# 07_MSM8916_GPIO.net
KiCad netlist of a schematic drawn in Altium Designer
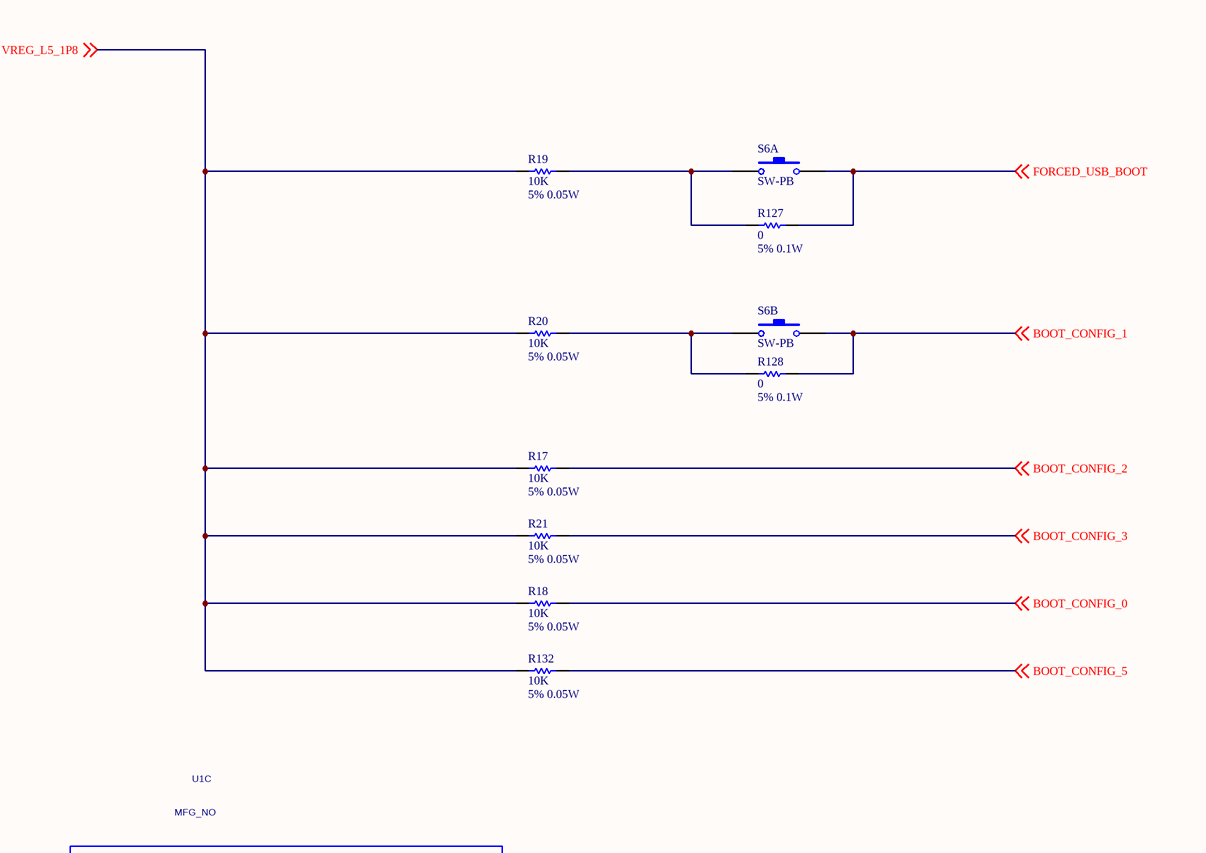
[diagram p0: 07_MSM8916_GPIO.SchDoc, top left]
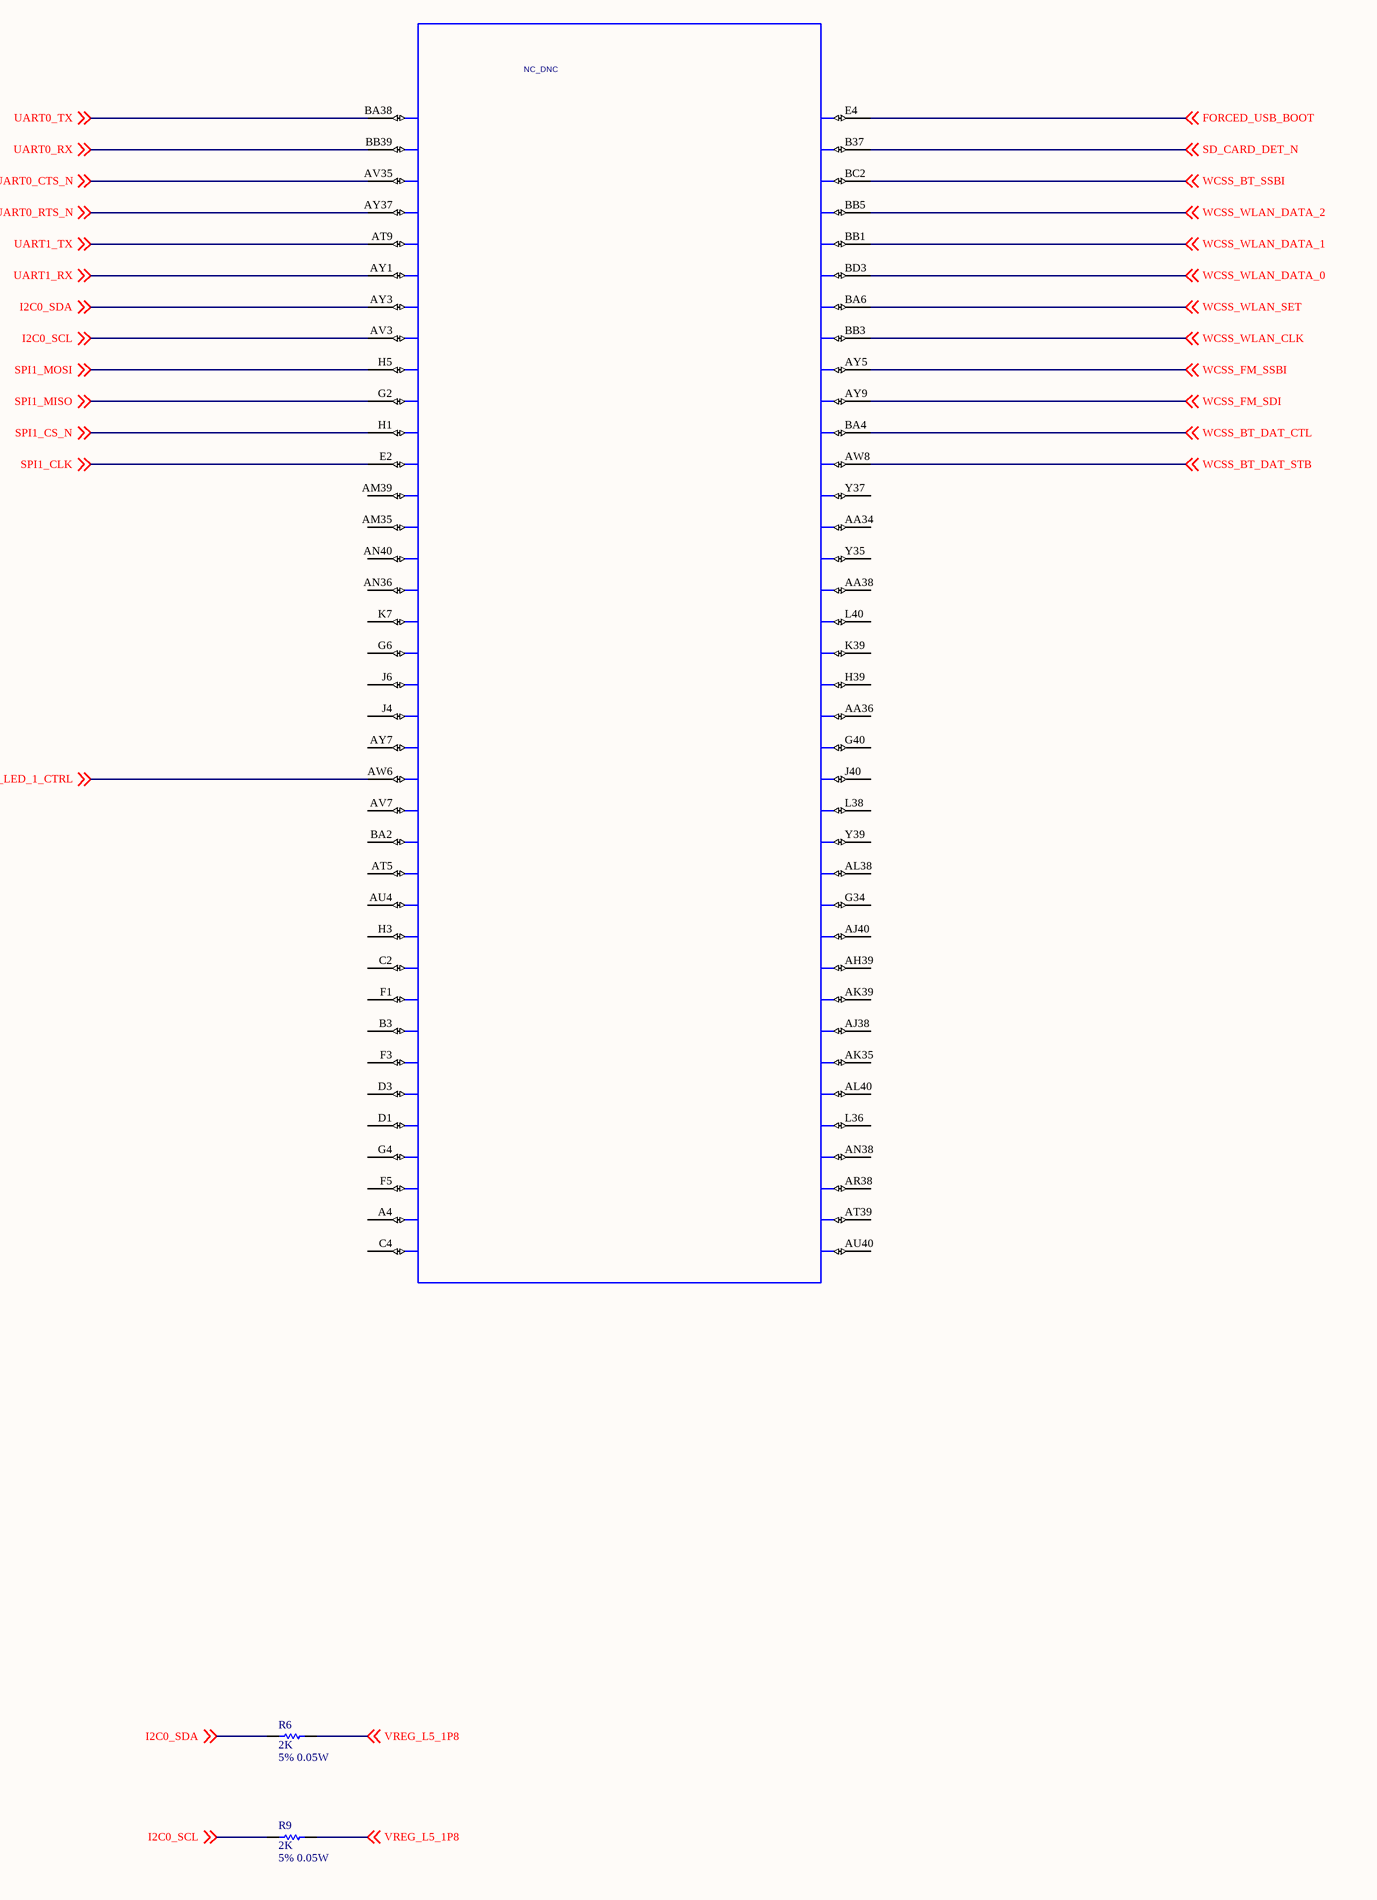
[diagram p1: 07_MSM8916_GPIO.SchDoc, bottom left]
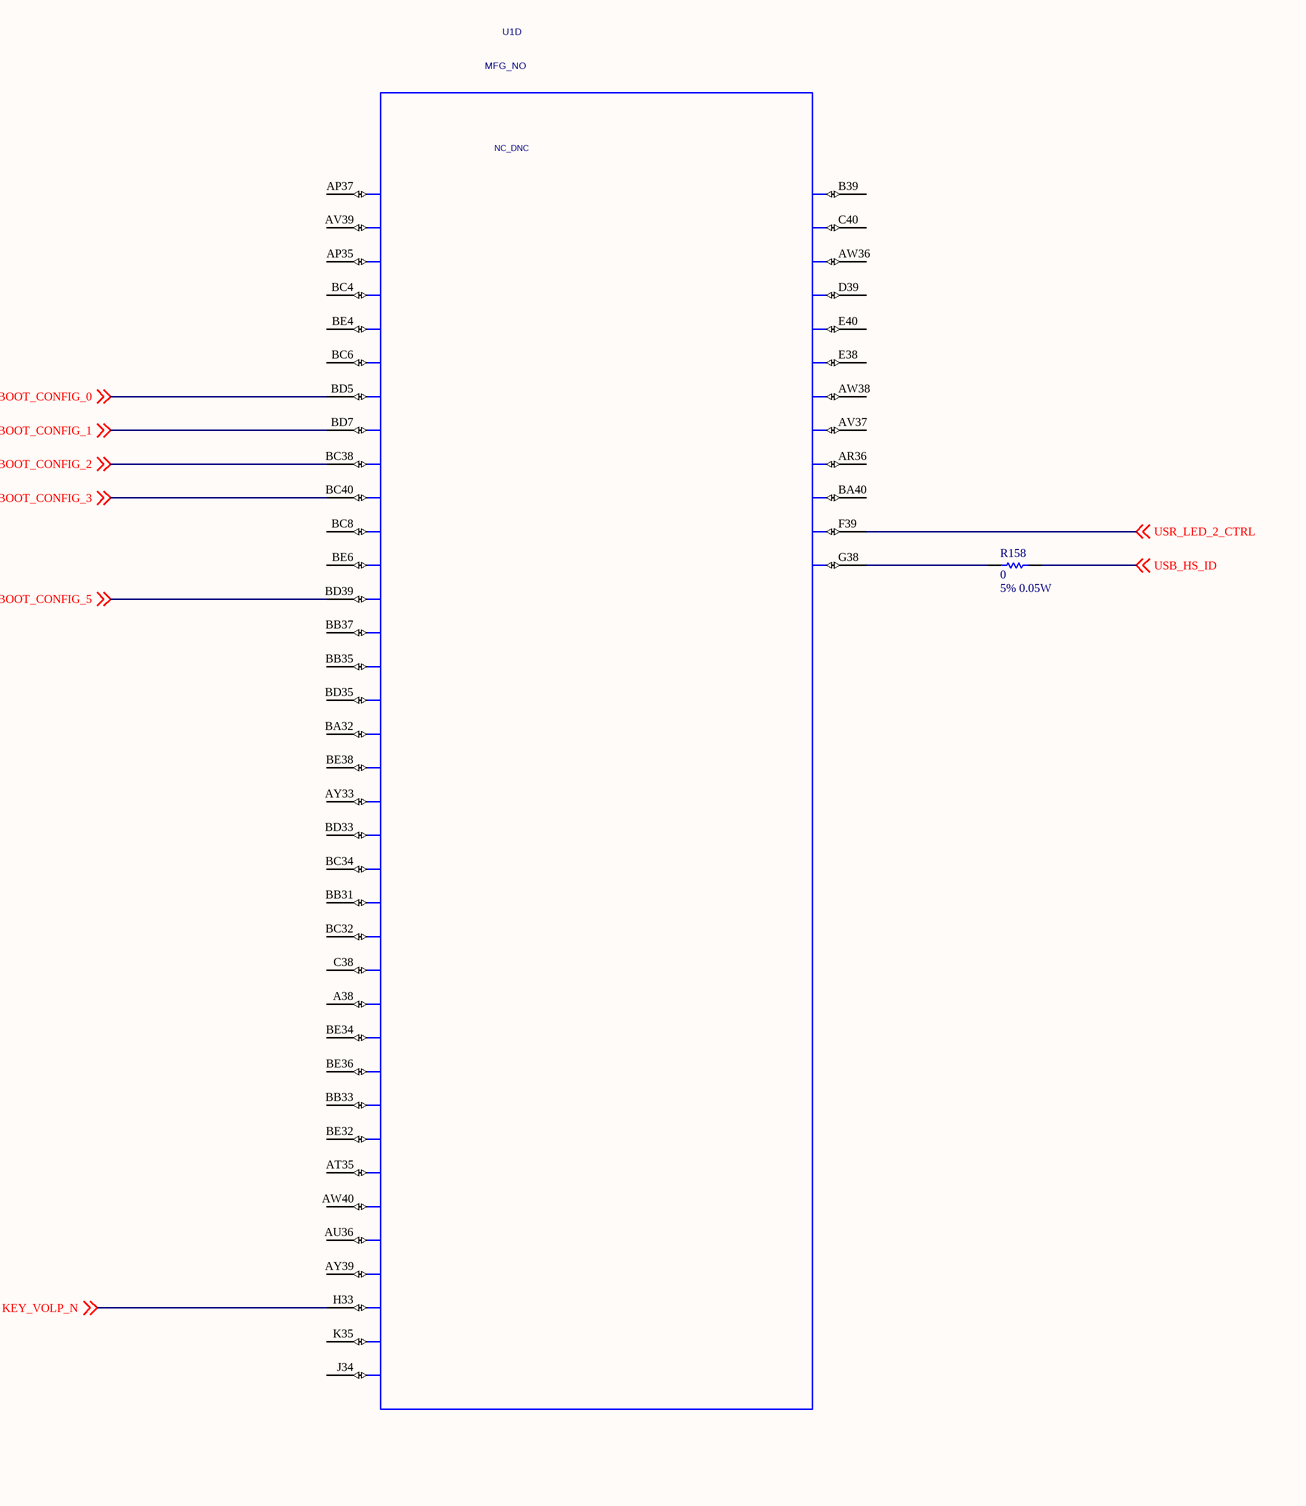
[diagram p2: 07_MSM8916_GPIO.SchDoc, bottom right]

(export (version "E")
  (design (tool "Eeschema 10.0.6"))
  (components
    (comp (ref "R6")
      (value "2K")
      (footprint "AXIAL-0.3")
      (description "Resistor")
      (fields (field (name "ALTIUM_VALUE") "5% 0.05W") (field (name "PUBLISHER") "Altium Limited"))
      (libsource (lib "Miscellaneous Devices") (part "Res1"))
    )
    (comp (ref "R9")
      (value "2K")
      (footprint "AXIAL-0.3")
      (description "Resistor")
      (fields (field (name "ALTIUM_VALUE") "5% 0.05W") (field (name "PUBLISHER") "Altium Limited"))
      (libsource (lib "Miscellaneous Devices") (part "Res1"))
    )
    (comp (ref "R17")
      (value "10K")
      (footprint "AXIAL-0.3")
      (description "Resistor")
      (fields (field (name "ALTIUM_VALUE") "5% 0.05W") (field (name "PUBLISHER") "Altium Limited"))
      (libsource (lib "Miscellaneous Devices") (part "Res1"))
    )
    (comp (ref "R18")
      (value "10K")
      (footprint "AXIAL-0.3")
      (description "Resistor")
      (fields (field (name "ALTIUM_VALUE") "5% 0.05W") (field (name "PUBLISHER") "Altium Limited"))
      (libsource (lib "Miscellaneous Devices") (part "Res1"))
    )
    (comp (ref "R19")
      (value "10K")
      (footprint "AXIAL-0.3")
      (description "Resistor")
      (fields (field (name "ALTIUM_VALUE") "5% 0.05W") (field (name "PUBLISHER") "Altium Limited"))
      (libsource (lib "Miscellaneous Devices") (part "Res1"))
    )
    (comp (ref "R20")
      (value "10K")
      (footprint "AXIAL-0.3")
      (description "Resistor")
      (fields (field (name "ALTIUM_VALUE") "5% 0.05W") (field (name "PUBLISHER") "Altium Limited"))
      (libsource (lib "Miscellaneous Devices") (part "Res1"))
    )
    (comp (ref "R21")
      (value "10K")
      (footprint "AXIAL-0.3")
      (description "Resistor")
      (fields (field (name "ALTIUM_VALUE") "5% 0.05W") (field (name "PUBLISHER") "Altium Limited"))
      (libsource (lib "Miscellaneous Devices") (part "Res1"))
    )
    (comp (ref "R127")
      (value "0")
      (footprint "AXIAL-0.3")
      (description "Resistor")
      (fields (field (name "ALTIUM_VALUE") "5% 0.1W") (field (name "PUBLISHER") "Altium Limited"))
      (libsource (lib "Miscellaneous Devices") (part "Res1"))
    )
    (comp (ref "R128")
      (value "0")
      (footprint "AXIAL-0.3")
      (description "Resistor")
      (fields (field (name "ALTIUM_VALUE") "5% 0.1W") (field (name "PUBLISHER") "Altium Limited"))
      (libsource (lib "Miscellaneous Devices") (part "Res1"))
    )
    (comp (ref "R132")
      (value "10K")
      (footprint "AXIAL-0.3")
      (description "Resistor")
      (fields (field (name "ALTIUM_VALUE") "5% 0.05W") (field (name "PUBLISHER") "Altium Limited"))
      (libsource (lib "Miscellaneous Devices") (part "Res1"))
    )
    (comp (ref "R158")
      (value "0")
      (footprint "AXIAL-0.3")
      (description "Resistor")
      (fields (field (name "ALTIUM_VALUE") "5% 0.05W") (field (name "PUBLISHER") "Altium Limited"))
      (libsource (lib "Miscellaneous Devices") (part "Res1"))
    )
    (comp (ref "S6A")
      (value "SW-PB")
      (footprint "SPST-2")
      (description "Switch")
      (fields (field (name "PUBLISHER") "Altium Limited"))
      (libsource (lib "Miscellaneous Devices") (part "SW-PB"))
    )
    (comp (ref "S6B")
      (value "SW-PB")
      (footprint "SPST-2")
      (description "Switch")
      (fields (field (name "PUBLISHER") "Altium Limited"))
      (libsource (lib "Miscellaneous Devices") (part "SW-PB"))
    )
    (comp (ref "U1")
      (value "ASIC_MSM8936_760PIN")
      (footprint "MSM-8916-0-760NSP-TR-00-0")
      (fields
        (field (name "PART_NUMBER") "MCN_NO")
        (field (name "SYMNAME") "NC_DNC")
        (field (name "PART_ID") "MFG_NO")
      )
      (libsource (lib "MSM8916_DRAM_PMIC_REF_Library") (part "ASIC_MSM8936_760PIN"))
    )
  )
  (nets
    (net (code "1") (name "BOOT_CONFIG_0") (class "Default")
      (node (ref "R18") (pin "2") (pinfunction "2_2") (pintype "passive"))
      (node (ref "U1") (pin "BD5") (pinfunction "GPIO_80_BD5") (pintype "bidirectional"))
    )
    (net (code "2") (name "BOOT_CONFIG_1") (class "Default")
      (node (ref "R128") (pin "2") (pinfunction "2_2") (pintype "passive"))
      (node (ref "S6B") (pin "2") (pinfunction "2_2") (pintype "passive"))
      (node (ref "U1") (pin "BD7") (pinfunction "GPIO_81_BD7") (pintype "bidirectional"))
    )
    (net (code "3") (name "BOOT_CONFIG_2") (class "Default")
      (node (ref "R17") (pin "2") (pinfunction "2_2") (pintype "passive"))
      (node (ref "U1") (pin "BC38") (pinfunction "GPIO_82_BC38") (pintype "bidirectional"))
    )
    (net (code "4") (name "BOOT_CONFIG_3") (class "Default")
      (node (ref "R21") (pin "2") (pinfunction "2_2") (pintype "passive"))
      (node (ref "U1") (pin "BC40") (pinfunction "GPIO_83_BC40") (pintype "bidirectional"))
    )
    (net (code "5") (name "BOOT_CONFIG_5") (class "Default")
      (node (ref "R132") (pin "2") (pinfunction "2_2") (pintype "passive"))
      (node (ref "U1") (pin "BD39") (pinfunction "GPIO_86_BD39") (pintype "bidirectional"))
    )
    (net (code "6") (name "FORCED_USB_BOOT") (class "Default")
      (node (ref "R127") (pin "2") (pinfunction "2_2") (pintype "passive"))
      (node (ref "S6A") (pin "2") (pinfunction "2_2") (pintype "passive"))
      (node (ref "U1") (pin "E4") (pinfunction "GPIO_37_E4") (pintype "bidirectional"))
    )
    (net (code "7") (name "I2C0_SCL") (class "Default")
      (node (ref "R9") (pin "2") (pinfunction "2_2") (pintype "passive"))
      (node (ref "U1") (pin "AV3") (pinfunction "GPIO_7_AV3") (pintype "bidirectional"))
    )
    (net (code "8") (name "I2C0_SDA") (class "Default")
      (node (ref "R6") (pin "2") (pinfunction "2_2") (pintype "passive"))
      (node (ref "U1") (pin "AY3") (pinfunction "GPIO_6_AY3") (pintype "bidirectional"))
    )
    (net (code "9") (name "KEY_VOLP_N") (class "Default")
      (node (ref "U1") (pin "H33") (pinfunction "GPIO_107_H33") (pintype "bidirectional"))
    )
    (net (code "10") (name "Net-(R127-Pad1)") (class "Default")
      (node (ref "R127") (pin "1") (pinfunction "1_1") (pintype "passive"))
      (node (ref "R19") (pin "2") (pinfunction "2_2") (pintype "passive"))
      (node (ref "S6A") (pin "1") (pinfunction "1_1") (pintype "passive"))
    )
    (net (code "11") (name "Net-(R128-Pad1)") (class "Default")
      (node (ref "R128") (pin "1") (pinfunction "1_1") (pintype "passive"))
      (node (ref "R20") (pin "2") (pinfunction "2_2") (pintype "passive"))
      (node (ref "S6B") (pin "1") (pinfunction "1_1") (pintype "passive"))
    )
    (net (code "12") (name "Net-(U1D-GPIO_121)") (class "Default")
      (node (ref "R158") (pin "1") (pinfunction "1_1") (pintype "passive"))
      (node (ref "U1") (pin "G38") (pinfunction "GPIO_121_G38") (pintype "bidirectional"))
    )
    (net (code "13") (name "SD_CARD_DET_N") (class "Default")
      (node (ref "U1") (pin "B37") (pinfunction "GPIO_38_B37") (pintype "bidirectional"))
    )
    (net (code "14") (name "SPI1_CLK") (class "Default")
      (node (ref "U1") (pin "E2") (pinfunction "GPIO_11_E2") (pintype "bidirectional"))
    )
    (net (code "15") (name "SPI1_CS_N") (class "Default")
      (node (ref "U1") (pin "H1") (pinfunction "GPIO_10_H1") (pintype "bidirectional"))
    )
    (net (code "16") (name "SPI1_MISO") (class "Default")
      (node (ref "U1") (pin "G2") (pinfunction "GPIO_9_G2") (pintype "bidirectional"))
    )
    (net (code "17") (name "SPI1_MOSI") (class "Default")
      (node (ref "U1") (pin "H5") (pinfunction "GPIO_8_H5") (pintype "bidirectional"))
    )
    (net (code "18") (name "UART0_CTS_N") (class "Default")
      (node (ref "U1") (pin "AV35") (pinfunction "GPIO_2_AV35") (pintype "bidirectional"))
    )
    (net (code "19") (name "UART0_RTS_N") (class "Default")
      (node (ref "U1") (pin "AY37") (pinfunction "GPIO_3_AY37") (pintype "bidirectional"))
    )
    (net (code "20") (name "UART0_RX") (class "Default")
      (node (ref "U1") (pin "BB39") (pinfunction "GPIO_1_BB39") (pintype "bidirectional"))
    )
    (net (code "21") (name "UART0_TX") (class "Default")
      (node (ref "U1") (pin "BA38") (pinfunction "GPIO_0_BA38") (pintype "bidirectional"))
    )
    (net (code "22") (name "UART1_RX") (class "Default")
      (node (ref "U1") (pin "AY1") (pinfunction "GPIO_5_AY1") (pintype "bidirectional"))
    )
    (net (code "23") (name "UART1_TX") (class "Default")
      (node (ref "U1") (pin "AT9") (pinfunction "GPIO_4_AT9") (pintype "bidirectional"))
    )
    (net (code "24") (name "USB_HS_ID") (class "Default")
      (node (ref "R158") (pin "2") (pinfunction "2_2") (pintype "passive"))
    )
    (net (code "25") (name "USR_LED_1_CTRL") (class "Default")
      (node (ref "U1") (pin "AW6") (pinfunction "GPIO_21_AW6") (pintype "bidirectional"))
    )
    (net (code "26") (name "USR_LED_2_CTRL") (class "Default")
      (node (ref "U1") (pin "F39") (pinfunction "GPIO_120_F39") (pintype "bidirectional"))
    )
    (net (code "27") (name "VREG_L5_1P8") (class "Default")
      (node (ref "R132") (pin "1") (pinfunction "1_1") (pintype "passive"))
      (node (ref "R17") (pin "1") (pinfunction "1_1") (pintype "passive"))
      (node (ref "R18") (pin "1") (pinfunction "1_1") (pintype "passive"))
      (node (ref "R19") (pin "1") (pinfunction "1_1") (pintype "passive"))
      (node (ref "R20") (pin "1") (pinfunction "1_1") (pintype "passive"))
      (node (ref "R21") (pin "1") (pinfunction "1_1") (pintype "passive"))
      (node (ref "R6") (pin "1") (pinfunction "1_1") (pintype "passive"))
      (node (ref "R9") (pin "1") (pinfunction "1_1") (pintype "passive"))
    )
    (net (code "28") (name "WCSS_BT_DAT_CTL") (class "Default")
      (node (ref "U1") (pin "BA4") (pinfunction "GPIO_47_BA4") (pintype "bidirectional"))
    )
    (net (code "29") (name "WCSS_BT_DAT_STB") (class "Default")
      (node (ref "U1") (pin "AW8") (pinfunction "GPIO_48_AW8") (pintype "bidirectional"))
    )
    (net (code "30") (name "WCSS_BT_SSBI") (class "Default")
      (node (ref "U1") (pin "BC2") (pinfunction "GPIO_39_BC2") (pintype "bidirectional"))
    )
    (net (code "31") (name "WCSS_FM_SDI") (class "Default")
      (node (ref "U1") (pin "AY9") (pinfunction "GPIO_46_AY9") (pintype "bidirectional"))
    )
    (net (code "32") (name "WCSS_FM_SSBI") (class "Default")
      (node (ref "U1") (pin "AY5") (pinfunction "GPIO_45_AY5") (pintype "bidirectional"))
    )
    (net (code "33") (name "WCSS_WLAN_CLK") (class "Default")
      (node (ref "U1") (pin "BB3") (pinfunction "GPIO_44_BB3") (pintype "bidirectional"))
    )
    (net (code "34") (name "WCSS_WLAN_DATA_0") (class "Default")
      (node (ref "U1") (pin "BD3") (pinfunction "GPIO_42_BD3") (pintype "bidirectional"))
    )
    (net (code "35") (name "WCSS_WLAN_DATA_1") (class "Default")
      (node (ref "U1") (pin "BB1") (pinfunction "GPIO_41_BB1") (pintype "bidirectional"))
    )
    (net (code "36") (name "WCSS_WLAN_DATA_2") (class "Default")
      (node (ref "U1") (pin "BB5") (pinfunction "GPIO_40_BB5") (pintype "bidirectional"))
    )
    (net (code "37") (name "WCSS_WLAN_SET") (class "Default")
      (node (ref "U1") (pin "BA6") (pinfunction "GPIO_43_BA6") (pintype "bidirectional"))
    )
    (net (code "38") (name "unconnected-(U1C-GPIO_12-PadAM39)") (class "Default")
      (node (ref "U1") (pin "AM39") (pinfunction "GPIO_12_AM39") (pintype "bidirectional"))
    )
    (net (code "39") (name "unconnected-(U1C-GPIO_13-PadAM35)") (class "Default")
      (node (ref "U1") (pin "AM35") (pinfunction "GPIO_13_AM35") (pintype "bidirectional"))
    )
    (net (code "40") (name "unconnected-(U1C-GPIO_14-PadAN40)") (class "Default")
      (node (ref "U1") (pin "AN40") (pinfunction "GPIO_14_AN40") (pintype "bidirectional"))
    )
    (net (code "41") (name "unconnected-(U1C-GPIO_15-PadAN36)") (class "Default")
      (node (ref "U1") (pin "AN36") (pinfunction "GPIO_15_AN36") (pintype "bidirectional"))
    )
    (net (code "42") (name "unconnected-(U1C-GPIO_16-PadK7)") (class "Default")
      (node (ref "U1") (pin "K7") (pinfunction "GPIO_16_K7") (pintype "bidirectional"))
    )
    (net (code "43") (name "unconnected-(U1C-GPIO_17-PadG6)") (class "Default")
      (node (ref "U1") (pin "G6") (pinfunction "GPIO_17_G6") (pintype "bidirectional"))
    )
    (net (code "44") (name "unconnected-(U1C-GPIO_18-PadJ6)") (class "Default")
      (node (ref "U1") (pin "J6") (pinfunction "GPIO_18_J6") (pintype "bidirectional"))
    )
    (net (code "45") (name "unconnected-(U1C-GPIO_19-PadJ4)") (class "Default")
      (node (ref "U1") (pin "J4") (pinfunction "GPIO_19_J4") (pintype "bidirectional"))
    )
    (net (code "46") (name "unconnected-(U1C-GPIO_20-PadAY7)") (class "Default")
      (node (ref "U1") (pin "AY7") (pinfunction "GPIO_20_AY7") (pintype "bidirectional"))
    )
    (net (code "47") (name "unconnected-(U1C-GPIO_22-PadAV7)") (class "Default")
      (node (ref "U1") (pin "AV7") (pinfunction "GPIO_22_AV7") (pintype "bidirectional"))
    )
    (net (code "48") (name "unconnected-(U1C-GPIO_23-PadBA2)") (class "Default")
      (node (ref "U1") (pin "BA2") (pinfunction "GPIO_23_BA2") (pintype "bidirectional"))
    )
    (net (code "49") (name "unconnected-(U1C-GPIO_24-PadAT5)") (class "Default")
      (node (ref "U1") (pin "AT5") (pinfunction "GPIO_24_AT5") (pintype "bidirectional"))
    )
    (net (code "50") (name "unconnected-(U1C-GPIO_25-PadAU4)") (class "Default")
      (node (ref "U1") (pin "AU4") (pinfunction "GPIO_25_AU4") (pintype "bidirectional"))
    )
    (net (code "51") (name "unconnected-(U1C-GPIO_26-PadH3)") (class "Default")
      (node (ref "U1") (pin "H3") (pinfunction "GPIO_26_H3") (pintype "bidirectional"))
    )
    (net (code "52") (name "unconnected-(U1C-GPIO_27-PadC2)") (class "Default")
      (node (ref "U1") (pin "C2") (pinfunction "GPIO_27_C2") (pintype "bidirectional"))
    )
    (net (code "53") (name "unconnected-(U1C-GPIO_28-PadF1)") (class "Default")
      (node (ref "U1") (pin "F1") (pinfunction "GPIO_28_F1") (pintype "bidirectional"))
    )
    (net (code "54") (name "unconnected-(U1C-GPIO_29-PadB3)") (class "Default")
      (node (ref "U1") (pin "B3") (pinfunction "GPIO_29_B3") (pintype "bidirectional"))
    )
    (net (code "55") (name "unconnected-(U1C-GPIO_30-PadF3)") (class "Default")
      (node (ref "U1") (pin "F3") (pinfunction "GPIO_30_F3") (pintype "bidirectional"))
    )
    (net (code "56") (name "unconnected-(U1C-GPIO_31-PadD3)") (class "Default")
      (node (ref "U1") (pin "D3") (pinfunction "GPIO_31_D3") (pintype "bidirectional"))
    )
    (net (code "57") (name "unconnected-(U1C-GPIO_32-PadD1)") (class "Default")
      (node (ref "U1") (pin "D1") (pinfunction "GPIO_32_D1") (pintype "bidirectional"))
    )
    (net (code "58") (name "unconnected-(U1C-GPIO_33-PadG4)") (class "Default")
      (node (ref "U1") (pin "G4") (pinfunction "GPIO_33_G4") (pintype "bidirectional"))
    )
    (net (code "59") (name "unconnected-(U1C-GPIO_34-PadF5)") (class "Default")
      (node (ref "U1") (pin "F5") (pinfunction "GPIO_34_F5") (pintype "bidirectional"))
    )
    (net (code "60") (name "unconnected-(U1C-GPIO_35-PadA4)") (class "Default")
      (node (ref "U1") (pin "A4") (pinfunction "GPIO_35_A4") (pintype "bidirectional"))
    )
    (net (code "61") (name "unconnected-(U1C-GPIO_36-PadC4)") (class "Default")
      (node (ref "U1") (pin "C4") (pinfunction "GPIO_36_C4") (pintype "bidirectional"))
    )
    (net (code "62") (name "unconnected-(U1C-GPIO_49-PadY37)") (class "Default")
      (node (ref "U1") (pin "Y37") (pinfunction "GPIO_49_Y37") (pintype "bidirectional"))
    )
    (net (code "63") (name "unconnected-(U1C-GPIO_50-PadAA34)") (class "Default")
      (node (ref "U1") (pin "AA34") (pinfunction "GPIO_50_AA34") (pintype "bidirectional"))
    )
    (net (code "64") (name "unconnected-(U1C-GPIO_51-PadY35)") (class "Default")
      (node (ref "U1") (pin "Y35") (pinfunction "GPIO_51_Y35") (pintype "bidirectional"))
    )
    (net (code "65") (name "unconnected-(U1C-GPIO_52-PadAA38)") (class "Default")
      (node (ref "U1") (pin "AA38") (pinfunction "GPIO_52_AA38") (pintype "bidirectional"))
    )
    (net (code "66") (name "unconnected-(U1C-GPIO_53-PadL40)") (class "Default")
      (node (ref "U1") (pin "L40") (pinfunction "GPIO_53_L40") (pintype "bidirectional"))
    )
    (net (code "67") (name "unconnected-(U1C-GPIO_54-PadK39)") (class "Default")
      (node (ref "U1") (pin "K39") (pinfunction "GPIO_54_K39") (pintype "bidirectional"))
    )
    (net (code "68") (name "unconnected-(U1C-GPIO_55-PadH39)") (class "Default")
      (node (ref "U1") (pin "H39") (pinfunction "GPIO_55_H39") (pintype "bidirectional"))
    )
    (net (code "69") (name "unconnected-(U1C-GPIO_56-PadAA36)") (class "Default")
      (node (ref "U1") (pin "AA36") (pinfunction "GPIO_56_AA36") (pintype "bidirectional"))
    )
    (net (code "70") (name "unconnected-(U1C-GPIO_57-PadG40)") (class "Default")
      (node (ref "U1") (pin "G40") (pinfunction "GPIO_57_G40") (pintype "bidirectional"))
    )
    (net (code "71") (name "unconnected-(U1C-GPIO_58-PadJ40)") (class "Default")
      (node (ref "U1") (pin "J40") (pinfunction "GPIO_58_J40") (pintype "bidirectional"))
    )
    (net (code "72") (name "unconnected-(U1C-GPIO_59-PadL38)") (class "Default")
      (node (ref "U1") (pin "L38") (pinfunction "GPIO_59_L38") (pintype "bidirectional"))
    )
    (net (code "73") (name "unconnected-(U1C-GPIO_60-PadY39)") (class "Default")
      (node (ref "U1") (pin "Y39") (pinfunction "GPIO_60_Y39") (pintype "bidirectional"))
    )
    (net (code "74") (name "unconnected-(U1C-GPIO_61-PadAL38)") (class "Default")
      (node (ref "U1") (pin "AL38") (pinfunction "GPIO_61_AL38") (pintype "bidirectional"))
    )
    (net (code "75") (name "unconnected-(U1C-GPIO_62-PadG34)") (class "Default")
      (node (ref "U1") (pin "G34") (pinfunction "GPIO_62_G34") (pintype "bidirectional"))
    )
    (net (code "76") (name "unconnected-(U1C-GPIO_63-PadAJ40)") (class "Default")
      (node (ref "U1") (pin "AJ40") (pinfunction "GPIO_63_AJ40") (pintype "bidirectional"))
    )
    (net (code "77") (name "unconnected-(U1C-GPIO_64-PadAH39)") (class "Default")
      (node (ref "U1") (pin "AH39") (pinfunction "GPIO_64_AH39") (pintype "bidirectional"))
    )
    (net (code "78") (name "unconnected-(U1C-GPIO_65-PadAK39)") (class "Default")
      (node (ref "U1") (pin "AK39") (pinfunction "GPIO_65_AK39") (pintype "bidirectional"))
    )
    (net (code "79") (name "unconnected-(U1C-GPIO_66-PadAJ38)") (class "Default")
      (node (ref "U1") (pin "AJ38") (pinfunction "GPIO_66_AJ38") (pintype "bidirectional"))
    )
    (net (code "80") (name "unconnected-(U1C-GPIO_67-PadAK35)") (class "Default")
      (node (ref "U1") (pin "AK35") (pinfunction "GPIO_67_AK35") (pintype "bidirectional"))
    )
    (net (code "81") (name "unconnected-(U1C-GPIO_68-PadAL40)") (class "Default")
      (node (ref "U1") (pin "AL40") (pinfunction "GPIO_68_AL40") (pintype "bidirectional"))
    )
    (net (code "82") (name "unconnected-(U1C-GPIO_69-PadL36)") (class "Default")
      (node (ref "U1") (pin "L36") (pinfunction "GPIO_69_L36") (pintype "bidirectional"))
    )
    (net (code "83") (name "unconnected-(U1C-GPIO_70-PadAN38)") (class "Default")
      (node (ref "U1") (pin "AN38") (pinfunction "GPIO_70_AN38") (pintype "bidirectional"))
    )
    (net (code "84") (name "unconnected-(U1C-GPIO_71-PadAR38)") (class "Default")
      (node (ref "U1") (pin "AR38") (pinfunction "GPIO_71_AR38") (pintype "bidirectional"))
    )
    (net (code "85") (name "unconnected-(U1C-GPIO_72-PadAT39)") (class "Default")
      (node (ref "U1") (pin "AT39") (pinfunction "GPIO_72_AT39") (pintype "bidirectional"))
    )
    (net (code "86") (name "unconnected-(U1C-GPIO_73-PadAU40)") (class "Default")
      (node (ref "U1") (pin "AU40") (pinfunction "GPIO_73_AU40") (pintype "bidirectional"))
    )
    (net (code "87") (name "unconnected-(U1D-GPIO_74-PadAP37)") (class "Default")
      (node (ref "U1") (pin "AP37") (pinfunction "GPIO_74_AP37") (pintype "bidirectional"))
    )
    (net (code "88") (name "unconnected-(U1D-GPIO_75-PadAV39)") (class "Default")
      (node (ref "U1") (pin "AV39") (pinfunction "GPIO_75_AV39") (pintype "bidirectional"))
    )
    (net (code "89") (name "unconnected-(U1D-GPIO_76-PadAP35)") (class "Default")
      (node (ref "U1") (pin "AP35") (pinfunction "GPIO_76_AP35") (pintype "bidirectional"))
    )
    (net (code "90") (name "unconnected-(U1D-GPIO_77-PadBC4)") (class "Default")
      (node (ref "U1") (pin "BC4") (pinfunction "GPIO_77_BC4") (pintype "bidirectional"))
    )
    (net (code "91") (name "unconnected-(U1D-GPIO_78-PadBE4)") (class "Default")
      (node (ref "U1") (pin "BE4") (pinfunction "GPIO_78_BE4") (pintype "bidirectional"))
    )
    (net (code "92") (name "unconnected-(U1D-GPIO_79-PadBC6)") (class "Default")
      (node (ref "U1") (pin "BC6") (pinfunction "GPIO_79_BC6") (pintype "bidirectional"))
    )
    (net (code "93") (name "unconnected-(U1D-GPIO_84-PadBC8)") (class "Default")
      (node (ref "U1") (pin "BC8") (pinfunction "GPIO_84_BC8") (pintype "bidirectional"))
    )
    (net (code "94") (name "unconnected-(U1D-GPIO_85-PadBE6)") (class "Default")
      (node (ref "U1") (pin "BE6") (pinfunction "GPIO_85_BE6") (pintype "bidirectional"))
    )
    (net (code "95") (name "unconnected-(U1D-GPIO_87-PadBB37)") (class "Default")
      (node (ref "U1") (pin "BB37") (pinfunction "GPIO_87_BB37") (pintype "bidirectional"))
    )
    (net (code "96") (name "unconnected-(U1D-GPIO_88-PadBB35)") (class "Default")
      (node (ref "U1") (pin "BB35") (pinfunction "GPIO_88_BB35") (pintype "bidirectional"))
    )
    (net (code "97") (name "unconnected-(U1D-GPIO_89-PadBD35)") (class "Default")
      (node (ref "U1") (pin "BD35") (pinfunction "GPIO_89_BD35") (pintype "bidirectional"))
    )
    (net (code "98") (name "unconnected-(U1D-GPIO_90-PadBA32)") (class "Default")
      (node (ref "U1") (pin "BA32") (pinfunction "GPIO_90_BA32") (pintype "bidirectional"))
    )
    (net (code "99") (name "unconnected-(U1D-GPIO_91-PadBE38)") (class "Default")
      (node (ref "U1") (pin "BE38") (pinfunction "GPIO_91_BE38") (pintype "bidirectional"))
    )
    (net (code "100") (name "unconnected-(U1D-GPIO_92-PadAY33)") (class "Default")
      (node (ref "U1") (pin "AY33") (pinfunction "GPIO_92_AY33") (pintype "bidirectional"))
    )
    (net (code "101") (name "unconnected-(U1D-GPIO_93-PadBD33)") (class "Default")
      (node (ref "U1") (pin "BD33") (pinfunction "GPIO_93_BD33") (pintype "bidirectional"))
    )
    (net (code "102") (name "unconnected-(U1D-GPIO_94-PadBC34)") (class "Default")
      (node (ref "U1") (pin "BC34") (pinfunction "GPIO_94_BC34") (pintype "bidirectional"))
    )
    (net (code "103") (name "unconnected-(U1D-GPIO_95-PadBB31)") (class "Default")
      (node (ref "U1") (pin "BB31") (pinfunction "GPIO_95_BB31") (pintype "bidirectional"))
    )
    (net (code "104") (name "unconnected-(U1D-GPIO_96-PadBC32)") (class "Default")
      (node (ref "U1") (pin "BC32") (pinfunction "GPIO_96_BC32") (pintype "bidirectional"))
    )
    (net (code "105") (name "unconnected-(U1D-GPIO_97-PadC38)") (class "Default")
      (node (ref "U1") (pin "C38") (pinfunction "GPIO_97_C38") (pintype "bidirectional"))
    )
    (net (code "106") (name "unconnected-(U1D-GPIO_98-PadA38)") (class "Default")
      (node (ref "U1") (pin "A38") (pinfunction "GPIO_98_A38") (pintype "bidirectional"))
    )
    (net (code "107") (name "unconnected-(U1D-GPIO_99-PadBE34)") (class "Default")
      (node (ref "U1") (pin "BE34") (pinfunction "GPIO_99_BE34") (pintype "bidirectional"))
    )
    (net (code "108") (name "unconnected-(U1D-GPIO_100-PadBE36)") (class "Default")
      (node (ref "U1") (pin "BE36") (pinfunction "GPIO_100_BE36") (pintype "bidirectional"))
    )
    (net (code "109") (name "unconnected-(U1D-GPIO_101-PadBB33)") (class "Default")
      (node (ref "U1") (pin "BB33") (pinfunction "GPIO_101_BB33") (pintype "bidirectional"))
    )
    (net (code "110") (name "unconnected-(U1D-GPIO_102-PadBE32)") (class "Default")
      (node (ref "U1") (pin "BE32") (pinfunction "GPIO_102_BE32") (pintype "bidirectional"))
    )
    (net (code "111") (name "unconnected-(U1D-GPIO_103-PadAT35)") (class "Default")
      (node (ref "U1") (pin "AT35") (pinfunction "GPIO_103_AT35") (pintype "bidirectional"))
    )
    (net (code "112") (name "unconnected-(U1D-GPIO_104-PadAW40)") (class "Default")
      (node (ref "U1") (pin "AW40") (pinfunction "GPIO_104_AW40") (pintype "bidirectional"))
    )
    (net (code "113") (name "unconnected-(U1D-GPIO_105-PadAU36)") (class "Default")
      (node (ref "U1") (pin "AU36") (pinfunction "GPIO_105_AU36") (pintype "bidirectional"))
    )
    (net (code "114") (name "unconnected-(U1D-GPIO_106-PadAY39)") (class "Default")
      (node (ref "U1") (pin "AY39") (pinfunction "GPIO_106_AY39") (pintype "bidirectional"))
    )
    (net (code "115") (name "unconnected-(U1D-GPIO_108-PadK35)") (class "Default")
      (node (ref "U1") (pin "K35") (pinfunction "GPIO_108_K35") (pintype "bidirectional"))
    )
    (net (code "116") (name "unconnected-(U1D-GPIO_109-PadJ34)") (class "Default")
      (node (ref "U1") (pin "J34") (pinfunction "GPIO_109_J34") (pintype "bidirectional"))
    )
    (net (code "117") (name "unconnected-(U1D-GPIO_110-PadB39)") (class "Default")
      (node (ref "U1") (pin "B39") (pinfunction "GPIO_110_B39") (pintype "bidirectional"))
    )
    (net (code "118") (name "unconnected-(U1D-GPIO_111-PadC40)") (class "Default")
      (node (ref "U1") (pin "C40") (pinfunction "GPIO_111_C40") (pintype "bidirectional"))
    )
    (net (code "119") (name "unconnected-(U1D-GPIO_112-PadAW36)") (class "Default")
      (node (ref "U1") (pin "AW36") (pinfunction "GPIO_112_AW36") (pintype "bidirectional"))
    )
    (net (code "120") (name "unconnected-(U1D-GPIO_113-PadD39)") (class "Default")
      (node (ref "U1") (pin "D39") (pinfunction "GPIO_113_D39") (pintype "bidirectional"))
    )
    (net (code "121") (name "unconnected-(U1D-GPIO_114-PadE40)") (class "Default")
      (node (ref "U1") (pin "E40") (pinfunction "GPIO_114_E40") (pintype "bidirectional"))
    )
    (net (code "122") (name "unconnected-(U1D-GPIO_115-PadE38)") (class "Default")
      (node (ref "U1") (pin "E38") (pinfunction "GPIO_115_E38") (pintype "bidirectional"))
    )
    (net (code "123") (name "unconnected-(U1D-GPIO_116-PadAW38)") (class "Default")
      (node (ref "U1") (pin "AW38") (pinfunction "GPIO_116_AW38") (pintype "bidirectional"))
    )
    (net (code "124") (name "unconnected-(U1D-GPIO_117-PadAV37)") (class "Default")
      (node (ref "U1") (pin "AV37") (pinfunction "GPIO_117_AV37") (pintype "bidirectional"))
    )
    (net (code "125") (name "unconnected-(U1D-GPIO_118-PadAR36)") (class "Default")
      (node (ref "U1") (pin "AR36") (pinfunction "GPIO_118_AR36") (pintype "bidirectional"))
    )
    (net (code "126") (name "unconnected-(U1D-GPIO_119-PadBA40)") (class "Default")
      (node (ref "U1") (pin "BA40") (pinfunction "GPIO_119_BA40") (pintype "bidirectional"))
    )
  )
)
